# Display.net
KiCad netlist of a schematic drawn in EAGLE
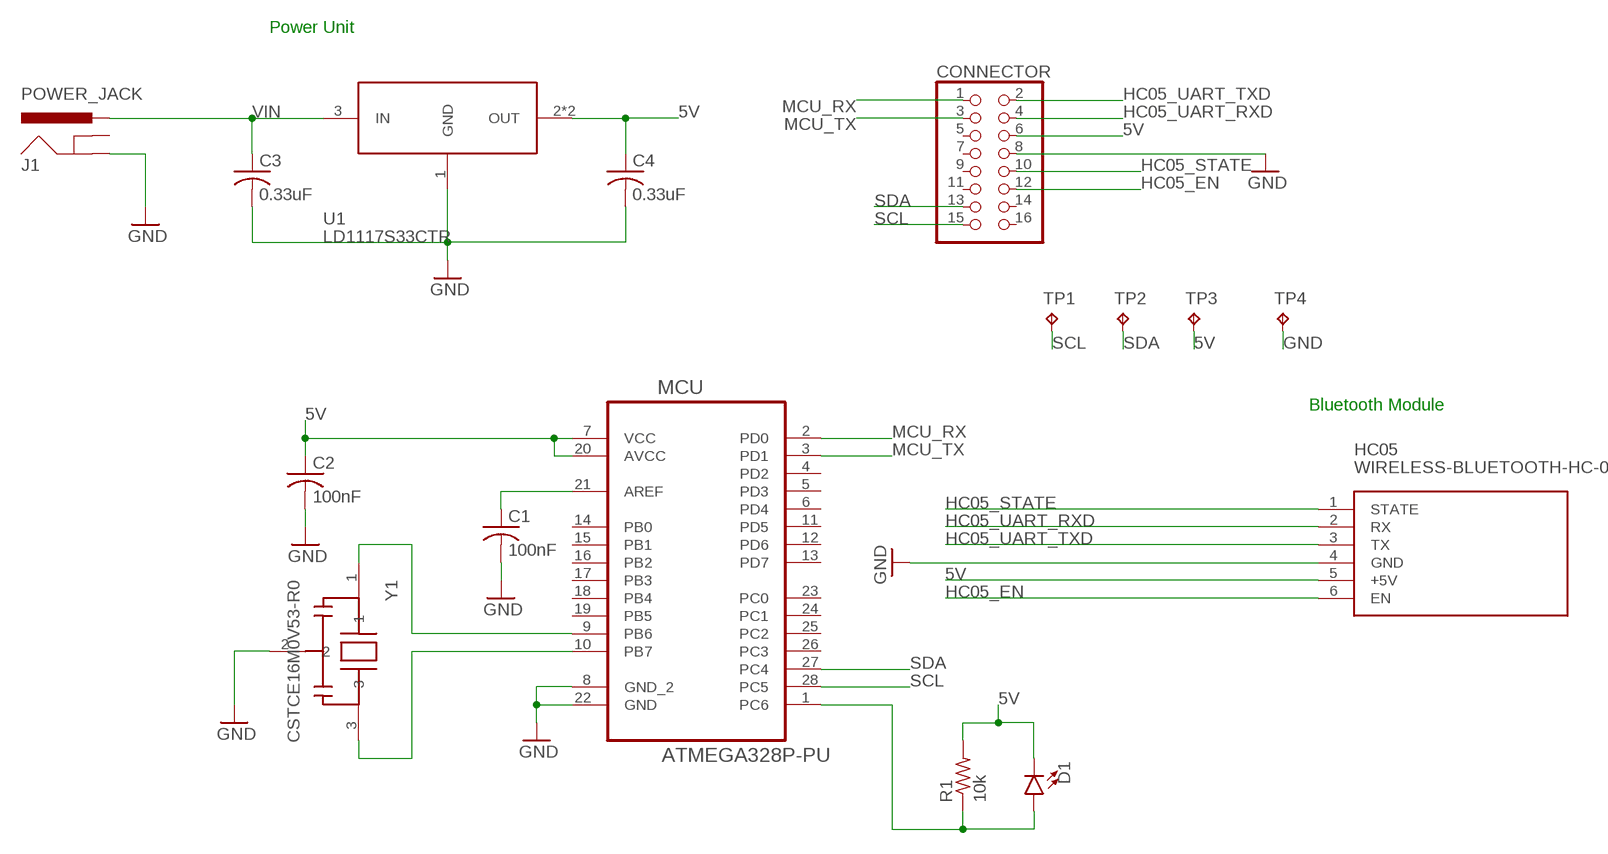
[diagram p0: schematic, sheet 1]

(export (version "E")
  (design (tool "Eeschema 10.0.6"))
  (components
    (comp (ref "C1")
      (value "100nF")
      (footprint "eagle-import:C0603")
      (libsource (lib "eagle-import") (part "C-USC0603"))
    )
    (comp (ref "C2")
      (value "100nF")
      (footprint "eagle-import:C0603")
      (libsource (lib "eagle-import") (part "C-USC0603"))
    )
    (comp (ref "C3")
      (value "0.33uF")
      (footprint "eagle-import:C0603")
      (libsource (lib "eagle-import") (part "C-USC0603"))
    )
    (comp (ref "C4")
      (value "0.33uF")
      (footprint "eagle-import:C0603")
      (libsource (lib "eagle-import") (part "C-USC0603"))
    )
    (comp (ref "CONNECTOR")
      (value "PINHD-2X8")
      (footprint "eagle-import:2X08")
      (libsource (lib "eagle-import") (part "PINHD-2X8"))
    )
    (comp (ref "D1")
      (value "LED1206")
      (footprint "eagle-import:LED-1206")
      (libsource (lib "eagle-import") (part "LED1206"))
    )
    (comp (ref "HC05")
      (value "WIRELESS-BLUETOOTH-HC-05")
      (footprint "eagle-import:WIRELESS-BLUETOOTH-HC-05")
      (libsource (lib "eagle-import") (part "WIRELESS-BLUETOOTH-HC-05"))
    )
    (comp (ref "J1")
      (value "POWER_JACK")
      (footprint "eagle-import:POWER_JACK_PTH")
      (libsource (lib "eagle-import") (part "POWER_JACK"))
    )
    (comp (ref "MCU")
      (value "ATMEGA328P-PU")
      (footprint "eagle-import:DIP254P762X457-28")
      (libsource (lib "eagle-import") (part "ATMEGA328P-PU"))
    )
    (comp (ref "R1")
      (value "10k")
      (footprint "eagle-import:R0603")
      (libsource (lib "eagle-import") (part "R-US_R0603"))
    )
    (comp (ref "TP1")
      (value "TPTP20R")
      (footprint "eagle-import:TP20R")
      (libsource (lib "eagle-import") (part "TPTP20R"))
    )
    (comp (ref "TP2")
      (value "TPTP20R")
      (footprint "eagle-import:TP20R")
      (libsource (lib "eagle-import") (part "TPTP20R"))
    )
    (comp (ref "TP3")
      (value "TPTP20R")
      (footprint "eagle-import:TP20R")
      (libsource (lib "eagle-import") (part "TPTP20R"))
    )
    (comp (ref "TP4")
      (value "TPTP20R")
      (footprint "eagle-import:TP20R")
      (libsource (lib "eagle-import") (part "TPTP20R"))
    )
    (comp (ref "U1")
      (value "LD1117S33CTR")
      (footprint "eagle-import:SOT223")
      (fields (field (name "MF") "STMicroelectronics"))
      (libsource (lib "eagle-import") (part "LD1117S33CTR"))
    )
    (comp (ref "Y1")
      (value "CSTCE16M0V53-R0")
      (footprint "eagle-import:OSC_CSTCE16M0V53-R0")
      (fields (field (name "MF") "Murata"))
      (libsource (lib "eagle-import") (part "CSTCE16M0V53-R0"))
    )
  )
  (nets
    (net (code "1") (name "/5V") (class "Default")
      (node (ref "C2") (pin "1") (pinfunction "1_1") (pintype "passive"))
      (node (ref "C4") (pin "1") (pinfunction "1_1") (pintype "passive"))
      (node (ref "CONNECTOR") (pin "6") (pinfunction "6_6") (pintype "passive"))
      (node (ref "D1") (pin "C") (pinfunction "C_C") (pintype "passive"))
      (node (ref "HC05") (pin "5") (pinfunction "+5V_5") (pintype "power_in"))
      (node (ref "MCU") (pin "20") (pinfunction "AVCC_20") (pintype "power_in"))
      (node (ref "MCU") (pin "7") (pinfunction "VCC_7") (pintype "power_in"))
      (node (ref "R1") (pin "2") (pinfunction "2_2") (pintype "passive"))
      (node (ref "TP3") (pin "TP") (pinfunction "TP_TP") (pintype "input"))
      (node (ref "U1") (pin "2") (pinfunction "OUT_2") (pintype "output"))
      (node (ref "U1") (pin "4") (pinfunction "OUT_4") (pintype "output"))
    )
    (net (code "2") (name "/HC05_EN") (class "Default")
      (node (ref "CONNECTOR") (pin "12") (pinfunction "12_12") (pintype "passive"))
      (node (ref "HC05") (pin "6") (pinfunction "EN_6") (pintype "bidirectional"))
    )
    (net (code "3") (name "/HC05_STATE") (class "Default")
      (node (ref "CONNECTOR") (pin "10") (pinfunction "10_10") (pintype "passive"))
      (node (ref "HC05") (pin "1") (pinfunction "STATE_1") (pintype "bidirectional"))
    )
    (net (code "4") (name "/HC05_UART_RXD") (class "Default")
      (node (ref "CONNECTOR") (pin "4") (pinfunction "4_4") (pintype "passive"))
      (node (ref "HC05") (pin "2") (pinfunction "RX_2") (pintype "bidirectional"))
    )
    (net (code "5") (name "/HC05_UART_TXD") (class "Default")
      (node (ref "CONNECTOR") (pin "2") (pinfunction "2_2") (pintype "passive"))
      (node (ref "HC05") (pin "3") (pinfunction "TX_3") (pintype "bidirectional"))
    )
    (net (code "6") (name "/MCU_RX") (class "Default")
      (node (ref "CONNECTOR") (pin "1") (pinfunction "1_1") (pintype "passive"))
      (node (ref "MCU") (pin "2") (pinfunction "PD0_2") (pintype "bidirectional"))
    )
    (net (code "7") (name "/MCU_TX") (class "Default")
      (node (ref "CONNECTOR") (pin "3") (pinfunction "3_3") (pintype "passive"))
      (node (ref "MCU") (pin "3") (pinfunction "PD1_3") (pintype "bidirectional"))
    )
    (net (code "8") (name "/SCL") (class "Default")
      (node (ref "CONNECTOR") (pin "15") (pinfunction "15_15") (pintype "passive"))
      (node (ref "MCU") (pin "28") (pinfunction "PC5_28") (pintype "bidirectional"))
      (node (ref "TP1") (pin "TP") (pinfunction "TP_TP") (pintype "input"))
    )
    (net (code "9") (name "/SDA") (class "Default")
      (node (ref "CONNECTOR") (pin "13") (pinfunction "13_13") (pintype "passive"))
      (node (ref "MCU") (pin "27") (pinfunction "PC4_27") (pintype "bidirectional"))
      (node (ref "TP2") (pin "TP") (pinfunction "TP_TP") (pintype "input"))
    )
    (net (code "10") (name "/VIN") (class "Default")
      (node (ref "C3") (pin "1") (pinfunction "1_1") (pintype "passive"))
      (node (ref "J1") (pin "PWR") (pinfunction "PWR_PWR") (pintype "bidirectional"))
      (node (ref "U1") (pin "3") (pinfunction "IN_3") (pintype "input"))
    )
    (net (code "11") (name "GND") (class "Default")
      (node (ref "C1") (pin "2") (pinfunction "2_2") (pintype "passive"))
      (node (ref "C2") (pin "2") (pinfunction "2_2") (pintype "passive"))
      (node (ref "C3") (pin "2") (pinfunction "2_2") (pintype "passive"))
      (node (ref "C4") (pin "2") (pinfunction "2_2") (pintype "passive"))
      (node (ref "CONNECTOR") (pin "8") (pinfunction "8_8") (pintype "passive"))
      (node (ref "HC05") (pin "4") (pinfunction "GND_4") (pintype "power_in"))
      (node (ref "J1") (pin "GND") (pinfunction "GND_GND") (pintype "bidirectional"))
      (node (ref "MCU") (pin "22") (pinfunction "GND_22") (pintype "passive"))
      (node (ref "MCU") (pin "8") (pinfunction "GND_2_8") (pintype "passive"))
      (node (ref "TP4") (pin "TP") (pinfunction "TP_TP") (pintype "input"))
      (node (ref "U1") (pin "1") (pinfunction "GND_1") (pintype "passive"))
      (node (ref "Y1") (pin "2") (pinfunction "2_2") (pintype "passive"))
    )
    (net (code "12") (name "Net-(MCU-AREF)") (class "Default")
      (node (ref "C1") (pin "1") (pinfunction "1_1") (pintype "passive"))
      (node (ref "MCU") (pin "21") (pinfunction "AREF_21") (pintype "input"))
    )
    (net (code "13") (name "Net-(MCU-PB6)") (class "Default")
      (node (ref "MCU") (pin "9") (pinfunction "PB6_9") (pintype "bidirectional"))
      (node (ref "Y1") (pin "1") (pinfunction "1_1") (pintype "input"))
    )
    (net (code "14") (name "Net-(MCU-PB7)") (class "Default")
      (node (ref "MCU") (pin "10") (pinfunction "PB7_10") (pintype "bidirectional"))
      (node (ref "Y1") (pin "3") (pinfunction "3_3") (pintype "output"))
    )
    (net (code "15") (name "Net-(MCU-PC6)") (class "Default")
      (node (ref "D1") (pin "A") (pinfunction "A_A") (pintype "passive"))
      (node (ref "MCU") (pin "1") (pinfunction "PC6_1") (pintype "bidirectional"))
      (node (ref "R1") (pin "1") (pinfunction "1_1") (pintype "passive"))
    )
    (net (code "16") (name "unconnected-(CONNECTOR-Pad5)") (class "Default")
      (node (ref "CONNECTOR") (pin "5") (pinfunction "5_5") (pintype "passive"))
    )
    (net (code "17") (name "unconnected-(CONNECTOR-Pad7)") (class "Default")
      (node (ref "CONNECTOR") (pin "7") (pinfunction "7_7") (pintype "passive"))
    )
    (net (code "18") (name "unconnected-(CONNECTOR-Pad9)") (class "Default")
      (node (ref "CONNECTOR") (pin "9") (pinfunction "9_9") (pintype "passive"))
    )
    (net (code "19") (name "unconnected-(CONNECTOR-Pad11)") (class "Default")
      (node (ref "CONNECTOR") (pin "11") (pinfunction "11_11") (pintype "passive"))
    )
    (net (code "20") (name "unconnected-(CONNECTOR-Pad14)") (class "Default")
      (node (ref "CONNECTOR") (pin "14") (pinfunction "14_14") (pintype "passive"))
    )
    (net (code "21") (name "unconnected-(CONNECTOR-Pad16)") (class "Default")
      (node (ref "CONNECTOR") (pin "16") (pinfunction "16_16") (pintype "passive"))
    )
    (net (code "22") (name "unconnected-(J1-PadGNDBREAK)") (class "Default")
      (node (ref "J1") (pin "GNDBREAK") (pinfunction "GNDBREAK_GNDBREAK") (pintype "bidirectional"))
    )
    (net (code "23") (name "unconnected-(MCU-PB0-Pad14)") (class "Default")
      (node (ref "MCU") (pin "14") (pinfunction "PB0_14") (pintype "bidirectional"))
    )
    (net (code "24") (name "unconnected-(MCU-PB1-Pad15)") (class "Default")
      (node (ref "MCU") (pin "15") (pinfunction "PB1_15") (pintype "bidirectional"))
    )
    (net (code "25") (name "unconnected-(MCU-PB2-Pad16)") (class "Default")
      (node (ref "MCU") (pin "16") (pinfunction "PB2_16") (pintype "bidirectional"))
    )
    (net (code "26") (name "unconnected-(MCU-PB3-Pad17)") (class "Default")
      (node (ref "MCU") (pin "17") (pinfunction "PB3_17") (pintype "bidirectional"))
    )
    (net (code "27") (name "unconnected-(MCU-PB4-Pad18)") (class "Default")
      (node (ref "MCU") (pin "18") (pinfunction "PB4_18") (pintype "bidirectional"))
    )
    (net (code "28") (name "unconnected-(MCU-PB5-Pad19)") (class "Default")
      (node (ref "MCU") (pin "19") (pinfunction "PB5_19") (pintype "bidirectional"))
    )
    (net (code "29") (name "unconnected-(MCU-PC0-Pad23)") (class "Default")
      (node (ref "MCU") (pin "23") (pinfunction "PC0_23") (pintype "bidirectional"))
    )
    (net (code "30") (name "unconnected-(MCU-PC1-Pad24)") (class "Default")
      (node (ref "MCU") (pin "24") (pinfunction "PC1_24") (pintype "bidirectional"))
    )
    (net (code "31") (name "unconnected-(MCU-PC2-Pad25)") (class "Default")
      (node (ref "MCU") (pin "25") (pinfunction "PC2_25") (pintype "bidirectional"))
    )
    (net (code "32") (name "unconnected-(MCU-PC3-Pad26)") (class "Default")
      (node (ref "MCU") (pin "26") (pinfunction "PC3_26") (pintype "bidirectional"))
    )
    (net (code "33") (name "unconnected-(MCU-PD2-Pad4)") (class "Default")
      (node (ref "MCU") (pin "4") (pinfunction "PD2_4") (pintype "bidirectional"))
    )
    (net (code "34") (name "unconnected-(MCU-PD3-Pad5)") (class "Default")
      (node (ref "MCU") (pin "5") (pinfunction "PD3_5") (pintype "bidirectional"))
    )
    (net (code "35") (name "unconnected-(MCU-PD4-Pad6)") (class "Default")
      (node (ref "MCU") (pin "6") (pinfunction "PD4_6") (pintype "bidirectional"))
    )
    (net (code "36") (name "unconnected-(MCU-PD5-Pad11)") (class "Default")
      (node (ref "MCU") (pin "11") (pinfunction "PD5_11") (pintype "bidirectional"))
    )
    (net (code "37") (name "unconnected-(MCU-PD6-Pad12)") (class "Default")
      (node (ref "MCU") (pin "12") (pinfunction "PD6_12") (pintype "bidirectional"))
    )
    (net (code "38") (name "unconnected-(MCU-PD7-Pad13)") (class "Default")
      (node (ref "MCU") (pin "13") (pinfunction "PD7_13") (pintype "bidirectional"))
    )
  )
)
